# Scott_Beck_PIC32_Schematic.net
KiCad netlist of a schematic drawn in EAGLE
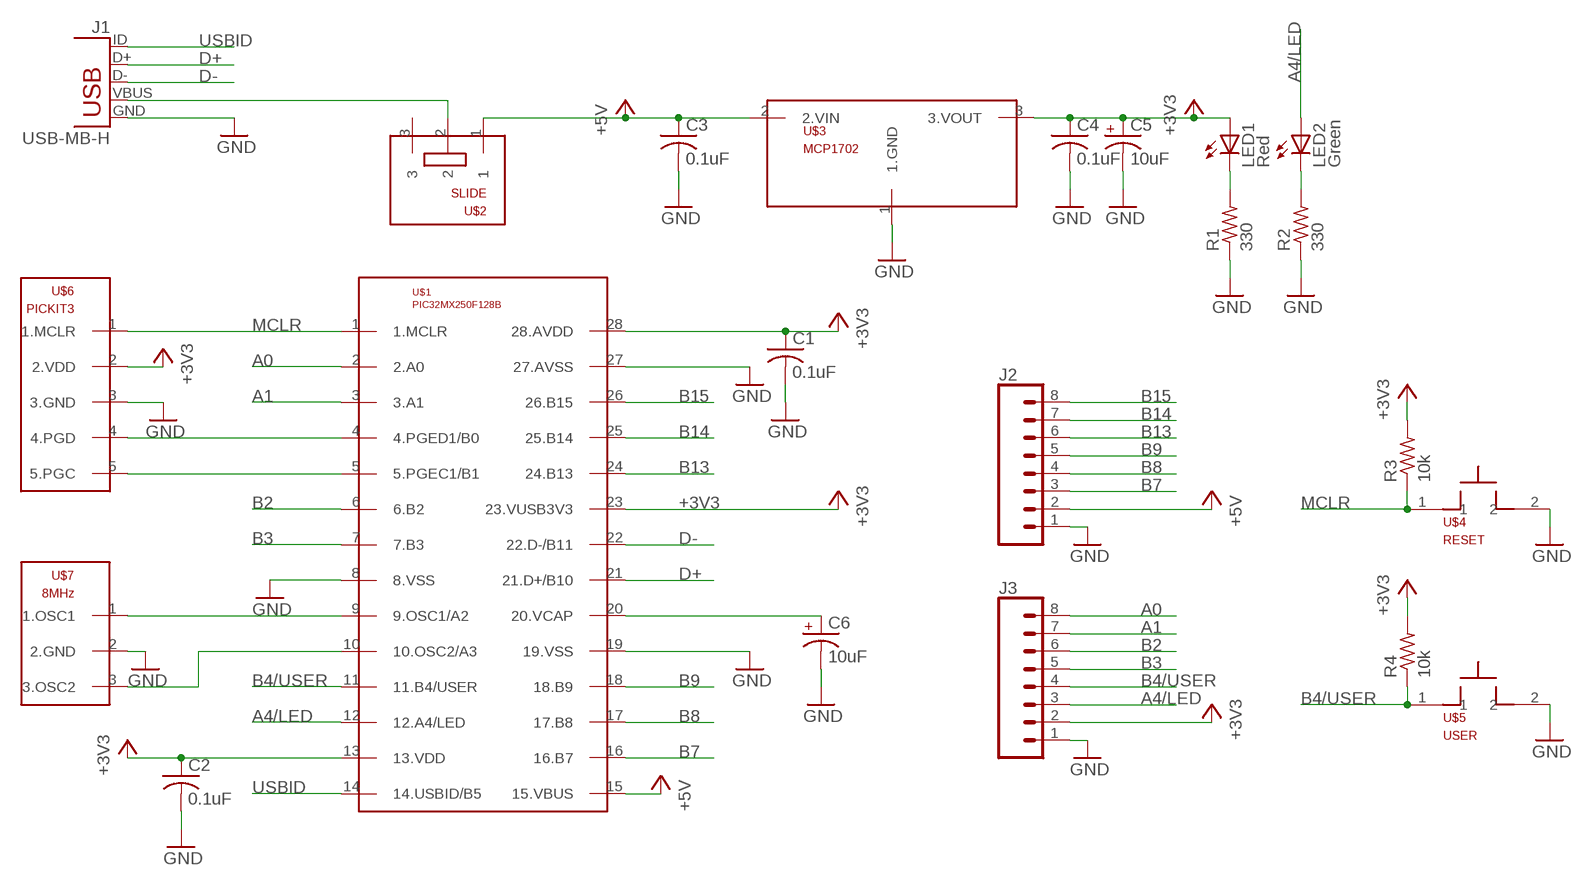
[diagram p0: schematic, sheet 1]

(export (version "E")
  (design (tool "Eeschema 10.0.6"))
  (components
    (comp (ref "C1")
      (value "0.1uF")
      (footprint "eagle-import:C0603")
      (libsource (lib "eagle-import") (part "C-USC0603"))
    )
    (comp (ref "C2")
      (value "0.1uF")
      (footprint "eagle-import:C0603")
      (libsource (lib "eagle-import") (part "C-USC0603"))
    )
    (comp (ref "C3")
      (value "0.1uF")
      (footprint "eagle-import:C0603")
      (libsource (lib "eagle-import") (part "C-USC0603"))
    )
    (comp (ref "C4")
      (value "0.1uF")
      (footprint "eagle-import:C0603")
      (libsource (lib "eagle-import") (part "C-USC0603"))
    )
    (comp (ref "C5")
      (value "10uF")
      (footprint "eagle-import:C0603")
      (libsource (lib "eagle-import") (part "C-USC0603"))
    )
    (comp (ref "C6")
      (value "10uF")
      (footprint "eagle-import:C0603")
      (libsource (lib "eagle-import") (part "C-USC0603"))
    )
    (comp (ref "J1")
      (value "USB-MB-H")
      (footprint "eagle-import:USB-MB-H")
      (libsource (lib "eagle-import") (part "USB-MB-H"))
    )
    (comp (ref "J2")
      (value "CONN_08\"")
      (footprint "eagle-import:1X08")
      (libsource (lib "eagle-import") (part "CONN_08{dblquote}"))
    )
    (comp (ref "J3")
      (value "CONN_08\"")
      (footprint "eagle-import:1X08")
      (libsource (lib "eagle-import") (part "CONN_08{dblquote}"))
    )
    (comp (ref "LED1")
      (value "Red")
      (footprint "eagle-import:SML0603")
      (libsource (lib "eagle-import") (part "LEDSML0603"))
    )
    (comp (ref "LED2")
      (value "Green")
      (footprint "eagle-import:SML0603")
      (libsource (lib "eagle-import") (part "LEDSML0603"))
    )
    (comp (ref "R1")
      (value "330")
      (footprint "eagle-import:R0603")
      (libsource (lib "eagle-import") (part "R-US_R0603"))
    )
    (comp (ref "R2")
      (value "330")
      (footprint "eagle-import:R0603")
      (libsource (lib "eagle-import") (part "R-US_R0603"))
    )
    (comp (ref "R3")
      (value "10k")
      (footprint "eagle-import:R0603")
      (libsource (lib "eagle-import") (part "R-US_R0603"))
    )
    (comp (ref "R4")
      (value "10k")
      (footprint "eagle-import:R0603")
      (libsource (lib "eagle-import") (part "R-US_R0603"))
    )
    (comp (ref "U$1")
      (value "PIC32MX250F128B")
      (footprint "eagle-import:DIL28-3")
      (libsource (lib "eagle-import") (part "PIC32MX250F128B"))
    )
    (comp (ref "U$2")
      (value "SLIDE")
      (footprint "eagle-import:SLIDE")
      (libsource (lib "eagle-import") (part "SLIDE"))
    )
    (comp (ref "U$3")
      (value "MCP1702")
      (footprint "eagle-import:TO92")
      (libsource (lib "eagle-import") (part "MCP1702"))
    )
    (comp (ref "U$4")
      (value "RESET")
      (footprint "eagle-import:PB")
      (libsource (lib "eagle-import") (part "PB"))
    )
    (comp (ref "U$5")
      (value "USER")
      (footprint "eagle-import:PB")
      (libsource (lib "eagle-import") (part "PB"))
    )
    (comp (ref "U$6")
      (value "PICKIT3")
      (footprint "eagle-import:PICKIT3")
      (libsource (lib "eagle-import") (part "PICKIT3"))
    )
    (comp (ref "U$7")
      (value "8MHz")
      (footprint "eagle-import:OSC")
      (libsource (lib "eagle-import") (part "OSC"))
    )
  )
  (nets
    (net (code "1") (name "+3V3") (class "Default")
      (node (ref "C1") (pin "1") (pinfunction "1_1") (pintype "passive"))
      (node (ref "C2") (pin "1") (pinfunction "1_1") (pintype "passive"))
      (node (ref "C4") (pin "1") (pinfunction "1_1") (pintype "passive"))
      (node (ref "C5") (pin "1") (pinfunction "1_1") (pintype "passive"))
      (node (ref "J3") (pin "2") (pinfunction "2_2") (pintype "passive"))
      (node (ref "LED1") (pin "A") (pinfunction "A_A") (pintype "passive"))
      (node (ref "R3") (pin "2") (pinfunction "2_2") (pintype "passive"))
      (node (ref "R4") (pin "2") (pinfunction "2_2") (pintype "passive"))
      (node (ref "U$1") (pin "13") (pinfunction "13.VDD_13") (pintype "bidirectional"))
      (node (ref "U$1") (pin "23") (pinfunction "23.VUSB3V3_23") (pintype "bidirectional"))
      (node (ref "U$1") (pin "28") (pinfunction "28.AVDD_28") (pintype "bidirectional"))
      (node (ref "U$3") (pin "3") (pinfunction "3.VOUT_3") (pintype "bidirectional"))
      (node (ref "U$6") (pin "2") (pinfunction "2.VDD_2") (pintype "bidirectional"))
    )
    (net (code "2") (name "+5V") (class "Default")
      (node (ref "C3") (pin "1") (pinfunction "1_1") (pintype "passive"))
      (node (ref "J2") (pin "2") (pinfunction "2_2") (pintype "passive"))
      (node (ref "U$1") (pin "15") (pinfunction "15.VBUS_15") (pintype "bidirectional"))
      (node (ref "U$2") (pin "1") (pinfunction "1_1") (pintype "bidirectional"))
      (node (ref "U$3") (pin "2") (pinfunction "2.VIN_2") (pintype "bidirectional"))
    )
    (net (code "3") (name "/A0") (class "Default")
      (node (ref "J3") (pin "8") (pinfunction "8_8") (pintype "passive"))
      (node (ref "U$1") (pin "2") (pinfunction "2.A0_2") (pintype "bidirectional"))
    )
    (net (code "4") (name "/A1") (class "Default")
      (node (ref "J3") (pin "7") (pinfunction "7_7") (pintype "passive"))
      (node (ref "U$1") (pin "3") (pinfunction "3.A1_3") (pintype "bidirectional"))
    )
    (net (code "5") (name "/A4{slash}LED") (class "Default")
      (node (ref "J3") (pin "3") (pinfunction "3_3") (pintype "passive"))
      (node (ref "LED2") (pin "A") (pinfunction "A_A") (pintype "passive"))
      (node (ref "U$1") (pin "12") (pinfunction "12.A4/LED_12") (pintype "bidirectional"))
    )
    (net (code "6") (name "/B2") (class "Default")
      (node (ref "J3") (pin "6") (pinfunction "6_6") (pintype "passive"))
      (node (ref "U$1") (pin "6") (pinfunction "6.B2_6") (pintype "bidirectional"))
    )
    (net (code "7") (name "/B3") (class "Default")
      (node (ref "J3") (pin "5") (pinfunction "5_5") (pintype "passive"))
      (node (ref "U$1") (pin "7") (pinfunction "7.B3_7") (pintype "bidirectional"))
    )
    (net (code "8") (name "/B4{slash}USER") (class "Default")
      (node (ref "J3") (pin "4") (pinfunction "4_4") (pintype "passive"))
      (node (ref "R4") (pin "1") (pinfunction "1_1") (pintype "passive"))
      (node (ref "U$1") (pin "11") (pinfunction "11.B4/USER_11") (pintype "bidirectional"))
      (node (ref "U$5") (pin "1") (pinfunction "1_1") (pintype "bidirectional"))
    )
    (net (code "9") (name "/B7") (class "Default")
      (node (ref "J2") (pin "3") (pinfunction "3_3") (pintype "passive"))
      (node (ref "U$1") (pin "16") (pinfunction "16.B7_16") (pintype "bidirectional"))
    )
    (net (code "10") (name "/B8") (class "Default")
      (node (ref "J2") (pin "4") (pinfunction "4_4") (pintype "passive"))
      (node (ref "U$1") (pin "17") (pinfunction "17.B8_17") (pintype "bidirectional"))
    )
    (net (code "11") (name "/B9") (class "Default")
      (node (ref "J2") (pin "5") (pinfunction "5_5") (pintype "passive"))
      (node (ref "U$1") (pin "18") (pinfunction "18.B9_18") (pintype "bidirectional"))
    )
    (net (code "12") (name "/B13") (class "Default")
      (node (ref "J2") (pin "6") (pinfunction "6_6") (pintype "passive"))
      (node (ref "U$1") (pin "24") (pinfunction "24.B13_24") (pintype "bidirectional"))
    )
    (net (code "13") (name "/B14") (class "Default")
      (node (ref "J2") (pin "7") (pinfunction "7_7") (pintype "passive"))
      (node (ref "U$1") (pin "25") (pinfunction "25.B14_25") (pintype "bidirectional"))
    )
    (net (code "14") (name "/B15") (class "Default")
      (node (ref "J2") (pin "8") (pinfunction "8_8") (pintype "passive"))
      (node (ref "U$1") (pin "26") (pinfunction "26.B15_26") (pintype "bidirectional"))
    )
    (net (code "15") (name "/D+") (class "Default")
      (node (ref "J1") (pin "D+") (pinfunction "D+_D+") (pintype "bidirectional"))
      (node (ref "U$1") (pin "21") (pinfunction "21.D+/B10_21") (pintype "bidirectional"))
    )
    (net (code "16") (name "/D-") (class "Default")
      (node (ref "J1") (pin "D-") (pinfunction "D-_D-") (pintype "bidirectional"))
      (node (ref "U$1") (pin "22") (pinfunction "22.D-/B11_22") (pintype "bidirectional"))
    )
    (net (code "17") (name "/MCLR") (class "Default")
      (node (ref "R3") (pin "1") (pinfunction "1_1") (pintype "passive"))
      (node (ref "U$1") (pin "1") (pinfunction "1.MCLR_1") (pintype "bidirectional"))
      (node (ref "U$4") (pin "1") (pinfunction "1_1") (pintype "bidirectional"))
      (node (ref "U$6") (pin "1") (pinfunction "1.MCLR_1") (pintype "bidirectional"))
    )
    (net (code "18") (name "/USBID") (class "Default")
      (node (ref "J1") (pin "ID") (pinfunction "ID_ID") (pintype "bidirectional"))
      (node (ref "U$1") (pin "14") (pinfunction "14.USBID/B5_14") (pintype "bidirectional"))
    )
    (net (code "19") (name "GND") (class "Default")
      (node (ref "C1") (pin "2") (pinfunction "2_2") (pintype "passive"))
      (node (ref "C2") (pin "2") (pinfunction "2_2") (pintype "passive"))
      (node (ref "C3") (pin "2") (pinfunction "2_2") (pintype "passive"))
      (node (ref "C4") (pin "2") (pinfunction "2_2") (pintype "passive"))
      (node (ref "C5") (pin "2") (pinfunction "2_2") (pintype "passive"))
      (node (ref "C6") (pin "2") (pinfunction "2_2") (pintype "passive"))
      (node (ref "J1") (pin "GND") (pinfunction "GND_GND") (pintype "bidirectional"))
      (node (ref "J2") (pin "1") (pinfunction "1_1") (pintype "passive"))
      (node (ref "J3") (pin "1") (pinfunction "1_1") (pintype "passive"))
      (node (ref "R1") (pin "1") (pinfunction "1_1") (pintype "passive"))
      (node (ref "R2") (pin "1") (pinfunction "1_1") (pintype "passive"))
      (node (ref "U$1") (pin "19") (pinfunction "19.VSS_19") (pintype "bidirectional"))
      (node (ref "U$1") (pin "27") (pinfunction "27.AVSS_27") (pintype "bidirectional"))
      (node (ref "U$1") (pin "8") (pinfunction "8.VSS_8") (pintype "bidirectional"))
      (node (ref "U$3") (pin "1") (pinfunction "1.GND_1") (pintype "bidirectional"))
      (node (ref "U$4") (pin "2") (pinfunction "2_2") (pintype "bidirectional"))
      (node (ref "U$5") (pin "2") (pinfunction "2_2") (pintype "bidirectional"))
      (node (ref "U$6") (pin "3") (pinfunction "3.GND_3") (pintype "bidirectional"))
      (node (ref "U$7") (pin "2") (pinfunction "2.GND_2") (pintype "bidirectional"))
    )
    (net (code "20") (name "Net-(J1-PadVBUS)") (class "Default")
      (node (ref "J1") (pin "VBUS") (pinfunction "VBUS_VBUS") (pintype "bidirectional"))
      (node (ref "U$2") (pin "2") (pinfunction "2_2") (pintype "bidirectional"))
    )
    (net (code "21") (name "Net-(LED1-PadC)") (class "Default")
      (node (ref "LED1") (pin "C") (pinfunction "C_C") (pintype "passive"))
      (node (ref "R1") (pin "2") (pinfunction "2_2") (pintype "passive"))
    )
    (net (code "22") (name "Net-(LED2-PadC)") (class "Default")
      (node (ref "LED2") (pin "C") (pinfunction "C_C") (pintype "passive"))
      (node (ref "R2") (pin "2") (pinfunction "2_2") (pintype "passive"))
    )
    (net (code "23") (name "Net-(U$1-4.PGED1{slash}B0)") (class "Default")
      (node (ref "U$1") (pin "4") (pinfunction "4.PGED1/B0_4") (pintype "bidirectional"))
      (node (ref "U$6") (pin "4") (pinfunction "4.PGD_4") (pintype "bidirectional"))
    )
    (net (code "24") (name "Net-(U$1-5.PGEC1{slash}B1)") (class "Default")
      (node (ref "U$1") (pin "5") (pinfunction "5.PGEC1/B1_5") (pintype "bidirectional"))
      (node (ref "U$6") (pin "5") (pinfunction "5.PGC_5") (pintype "bidirectional"))
    )
    (net (code "25") (name "Net-(U$1-9.OSC1{slash}A2)") (class "Default")
      (node (ref "U$1") (pin "9") (pinfunction "9.OSC1/A2_9") (pintype "bidirectional"))
      (node (ref "U$7") (pin "1") (pinfunction "1.OSC1_1") (pintype "bidirectional"))
    )
    (net (code "26") (name "Net-(U$1-10.OSC2{slash}A3)") (class "Default")
      (node (ref "U$1") (pin "10") (pinfunction "10.OSC2/A3_10") (pintype "bidirectional"))
      (node (ref "U$7") (pin "3") (pinfunction "3.OSC2_3") (pintype "bidirectional"))
    )
    (net (code "27") (name "Net-(U$1-20.VCAP)") (class "Default")
      (node (ref "C6") (pin "1") (pinfunction "1_1") (pintype "passive"))
      (node (ref "U$1") (pin "20") (pinfunction "20.VCAP_20") (pintype "bidirectional"))
    )
    (net (code "28") (name "unconnected-(U$2-Pad3)") (class "Default")
      (node (ref "U$2") (pin "3") (pinfunction "3_3") (pintype "bidirectional"))
    )
  )
)
